# AX-03.net
KiCad netlist of a schematic drawn in EAGLE
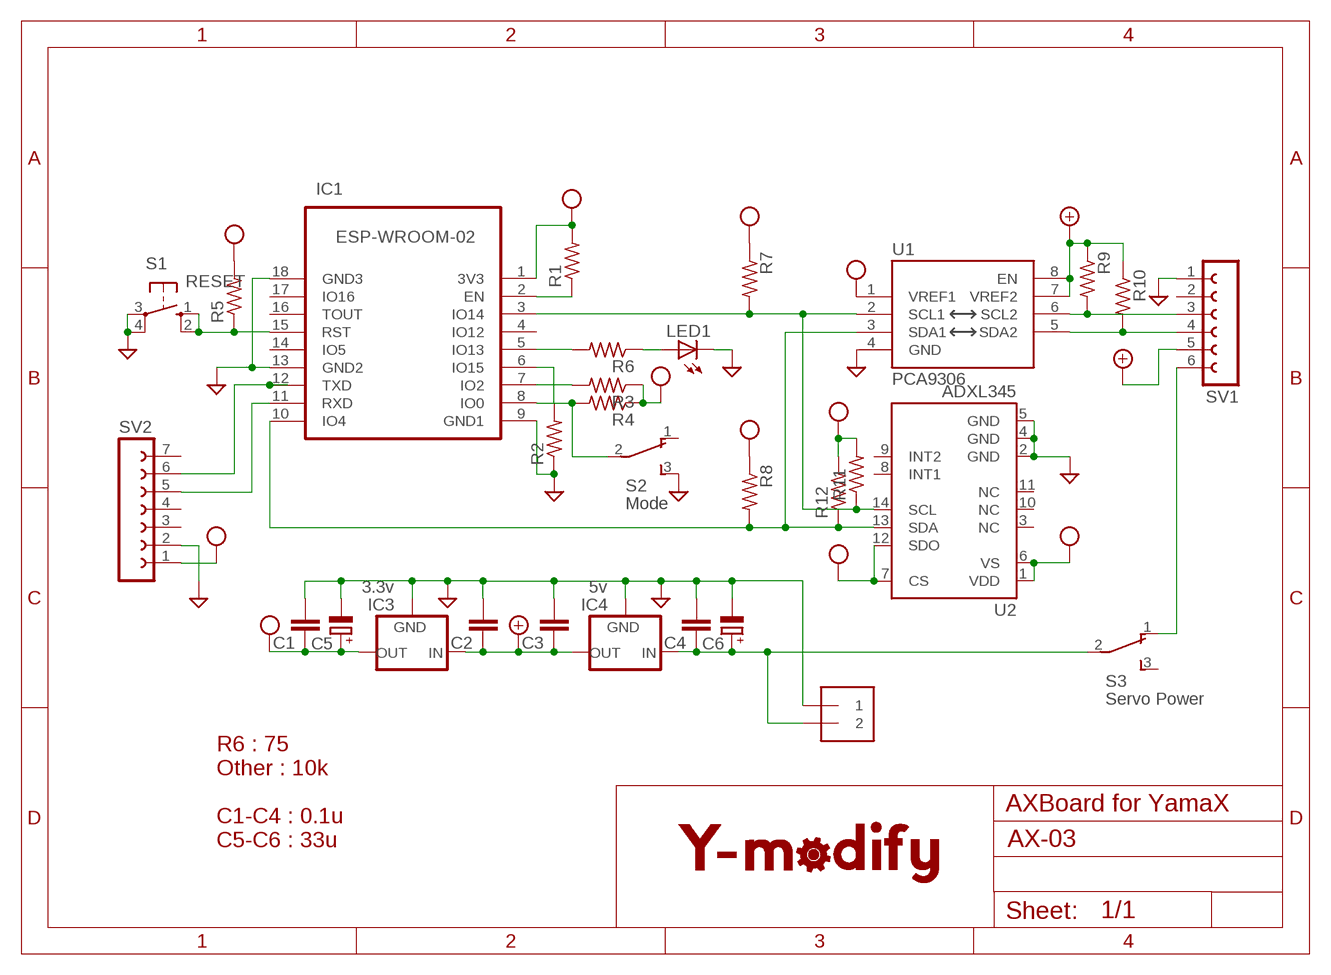
[diagram p0: schematic, sheet 1]

(export (version "E")
  (design (tool "Eeschema 10.0.6"))
  (components
    (comp (ref "C1")
      (value "C-EU025-024X044")
      (footprint "eagle-import:C025-024X044")
      (libsource (lib "eagle-import") (part "C-EU025-024X044"))
    )
    (comp (ref "C2")
      (value "C-EU025-024X044")
      (footprint "eagle-import:C025-024X044")
      (libsource (lib "eagle-import") (part "C-EU025-024X044"))
    )
    (comp (ref "C3")
      (value "C-EU025-024X044")
      (footprint "eagle-import:C025-024X044")
      (libsource (lib "eagle-import") (part "C-EU025-024X044"))
    )
    (comp (ref "C4")
      (value "C-EU025-024X044")
      (footprint "eagle-import:C025-024X044")
      (libsource (lib "eagle-import") (part "C-EU025-024X044"))
    )
    (comp (ref "C5")
      (value "CPOL-EUE5-8.5")
      (footprint "eagle-import:E5-8,5")
      (libsource (lib "eagle-import") (part "CPOL-EUE5-8.5"))
    )
    (comp (ref "C6")
      (value "CPOL-EUE5-8.5")
      (footprint "eagle-import:E5-8,5")
      (libsource (lib "eagle-import") (part "CPOL-EUE5-8.5"))
    )
    (comp (ref "IC1")
      (value "ESP-WROOM-02")
      (footprint "eagle-import:FRONT-FACE")
      (libsource (lib "eagle-import") (part "ESP-WROOM-02FRONT-FACE"))
    )
    (comp (ref "IC3")
      (value "3.3v")
      (footprint "eagle-import:78XXL")
      (libsource (lib "eagle-import") (part "78XXL"))
    )
    (comp (ref "IC4")
      (value "5v")
      (footprint "eagle-import:78XXL")
      (libsource (lib "eagle-import") (part "78XXL"))
    )
    (comp (ref "J1")
      (value "1X2-3.5MM")
      (footprint "eagle-import:1X2-3.5MM")
      (libsource (lib "eagle-import") (part "1X2-3.5MM"))
    )
    (comp (ref "LED1")
      (value "LED3MM")
      (footprint "eagle-import:LED3MM")
      (libsource (lib "eagle-import") (part "LED3MM"))
    )
    (comp (ref "R1")
      (value "R-US_0204/7")
      (footprint "eagle-import:0204_7")
      (libsource (lib "eagle-import") (part "R-US_0204/7"))
    )
    (comp (ref "R2")
      (value "R-US_0204/7")
      (footprint "eagle-import:0204_7")
      (libsource (lib "eagle-import") (part "R-US_0204/7"))
    )
    (comp (ref "R3")
      (value "R-US_0204/7")
      (footprint "eagle-import:0204_7")
      (libsource (lib "eagle-import") (part "R-US_0204/7"))
    )
    (comp (ref "R4")
      (value "R-US_0204/7")
      (footprint "eagle-import:0204_7")
      (libsource (lib "eagle-import") (part "R-US_0204/7"))
    )
    (comp (ref "R5")
      (value "R-US_0204/7")
      (footprint "eagle-import:0204_7")
      (libsource (lib "eagle-import") (part "R-US_0204/7"))
    )
    (comp (ref "R6")
      (value "R-US_0204/7")
      (footprint "eagle-import:0204_7")
      (libsource (lib "eagle-import") (part "R-US_0204/7"))
    )
    (comp (ref "R7")
      (value "R-US_0204/7")
      (footprint "eagle-import:0204_7")
      (libsource (lib "eagle-import") (part "R-US_0204/7"))
    )
    (comp (ref "R8")
      (value "R-US_0204/7")
      (footprint "eagle-import:0204_7")
      (libsource (lib "eagle-import") (part "R-US_0204/7"))
    )
    (comp (ref "R9")
      (value "R-US_0204/7")
      (footprint "eagle-import:0204_7")
      (libsource (lib "eagle-import") (part "R-US_0204/7"))
    )
    (comp (ref "R10")
      (value "R-US_0204/7")
      (footprint "eagle-import:0204_7")
      (libsource (lib "eagle-import") (part "R-US_0204/7"))
    )
    (comp (ref "R11")
      (value "R-US_0204/7")
      (footprint "eagle-import:0204_7")
      (libsource (lib "eagle-import") (part "R-US_0204/7"))
    )
    (comp (ref "R12")
      (value "R-US_0204/7")
      (footprint "eagle-import:0204_7")
      (libsource (lib "eagle-import") (part "R-US_0204/7"))
    )
    (comp (ref "S1")
      (value "RESET")
      (footprint "eagle-import:B3F-10XX")
      (fields (field (name "MPN") "B3F-1000"))
      (libsource (lib "eagle-import") (part "10-XX"))
    )
    (comp (ref "S2")
      (value "Mode")
      (footprint "eagle-import:TL3XYO")
      (libsource (lib "eagle-import") (part "TL36YO"))
    )
    (comp (ref "S3")
      (value "Servo Power")
      (footprint "eagle-import:TL3XYO")
      (libsource (lib "eagle-import") (part "TL36YO"))
    )
    (comp (ref "SV1")
      (value "FE06-1")
      (footprint "eagle-import:FE06")
      (libsource (lib "eagle-import") (part "FE06-1"))
    )
    (comp (ref "SV2")
      (value "FE07-1")
      (footprint "eagle-import:FE07")
      (libsource (lib "eagle-import") (part "FE07-1"))
    )
    (comp (ref "U$1")
      (value "Y-MODIFY")
      (footprint "eagle-import:Y-MODIFY")
      (libsource (lib "eagle-import") (part "Y-MODIFY"))
    )
    (comp (ref "U1")
      (value "PCA9306")
      (footprint "eagle-import:PSOP-8")
      (libsource (lib "eagle-import") (part "PCA9306"))
    )
    (comp (ref "U2")
      (value "ADXL345")
      (footprint "eagle-import:LGA14")
      (libsource (lib "eagle-import") (part "ADXL345"))
    )
  )
  (nets
    (net (code "1") (name "+5V") (class "Default")
      (node (ref "C2") (pin "1") (pinfunction "1_1") (pintype "passive"))
      (node (ref "C3") (pin "1") (pinfunction "1_1") (pintype "passive"))
      (node (ref "IC3") (pin "IN") (pinfunction "IN_IN") (pintype "input"))
      (node (ref "IC4") (pin "OUT") (pinfunction "OUT_OUT") (pintype "passive"))
      (node (ref "R10") (pin "1") (pinfunction "1_1") (pintype "passive"))
      (node (ref "R9") (pin "1") (pinfunction "1_1") (pintype "passive"))
      (node (ref "SV1") (pin "5") (pinfunction "5_5") (pintype "passive"))
      (node (ref "U1") (pin "7") (pinfunction "VREF2_7") (pintype "bidirectional"))
      (node (ref "U1") (pin "8") (pinfunction "EN_8") (pintype "bidirectional"))
    )
    (net (code "2") (name "GND") (class "Default")
      (node (ref "C1") (pin "2") (pinfunction "2_2") (pintype "passive"))
      (node (ref "C2") (pin "2") (pinfunction "2_2") (pintype "passive"))
      (node (ref "C3") (pin "2") (pinfunction "2_2") (pintype "passive"))
      (node (ref "C4") (pin "2") (pinfunction "2_2") (pintype "passive"))
      (node (ref "C5") (pin "-") (pinfunction "-_-") (pintype "passive"))
      (node (ref "C6") (pin "-") (pinfunction "-_-") (pintype "passive"))
      (node (ref "IC1") (pin "13") (pinfunction "GND2_13") (pintype "power_in"))
      (node (ref "IC1") (pin "18") (pinfunction "GND3_18") (pintype "power_in"))
      (node (ref "IC1") (pin "9") (pinfunction "GND1_9") (pintype "power_in"))
      (node (ref "IC3") (pin "GND") (pinfunction "GND_GND") (pintype "input"))
      (node (ref "IC4") (pin "GND") (pinfunction "GND_GND") (pintype "input"))
      (node (ref "J1") (pin "1") (pinfunction "1_1") (pintype "passive"))
      (node (ref "LED1") (pin "K") (pinfunction "C_K") (pintype "passive"))
      (node (ref "R2") (pin "1") (pinfunction "1_1") (pintype "passive"))
      (node (ref "S1") (pin "3") (pinfunction "P_3") (pintype "passive"))
      (node (ref "S1") (pin "4") (pinfunction "P1_4") (pintype "passive"))
      (node (ref "S2") (pin "3") (pinfunction "S_3") (pintype "passive"))
      (node (ref "SV1") (pin "1") (pinfunction "1_1") (pintype "passive"))
      (node (ref "SV2") (pin "2") (pinfunction "2_2") (pintype "passive"))
      (node (ref "U1") (pin "4") (pinfunction "GND_4") (pintype "bidirectional"))
      (node (ref "U2") (pin "2") (pinfunction "GND_2") (pintype "bidirectional"))
      (node (ref "U2") (pin "4") (pinfunction "GND_4") (pintype "bidirectional"))
      (node (ref "U2") (pin "5") (pinfunction "GND_5") (pintype "bidirectional"))
    )
    (net (code "3") (name "Net-(IC1-EN)") (class "Default")
      (node (ref "IC1") (pin "2") (pinfunction "EN_2") (pintype "bidirectional"))
      (node (ref "R1") (pin "1") (pinfunction "1_1") (pintype "passive"))
    )
    (net (code "4") (name "Net-(IC1-IO0)") (class "Default")
      (node (ref "IC1") (pin "8") (pinfunction "IO0_8") (pintype "bidirectional"))
      (node (ref "R4") (pin "2") (pinfunction "2_2") (pintype "passive"))
      (node (ref "S2") (pin "2") (pinfunction "P_2") (pintype "passive"))
    )
    (net (code "5") (name "Net-(IC1-IO2)") (class "Default")
      (node (ref "IC1") (pin "7") (pinfunction "IO2_7") (pintype "bidirectional"))
      (node (ref "R3") (pin "2") (pinfunction "2_2") (pintype "passive"))
    )
    (net (code "6") (name "Net-(IC1-IO4)") (class "Default")
      (node (ref "IC1") (pin "10") (pinfunction "IO4_10") (pintype "bidirectional"))
      (node (ref "R12") (pin "1") (pinfunction "1_1") (pintype "passive"))
      (node (ref "R8") (pin "2") (pinfunction "2_2") (pintype "passive"))
      (node (ref "U1") (pin "3") (pinfunction "SDA1_3") (pintype "bidirectional"))
      (node (ref "U2") (pin "13") (pinfunction "SDA_13") (pintype "bidirectional"))
    )
    (net (code "7") (name "Net-(IC1-IO13)") (class "Default")
      (node (ref "IC1") (pin "5") (pinfunction "IO13_5") (pintype "bidirectional"))
      (node (ref "R6") (pin "2") (pinfunction "2_2") (pintype "passive"))
    )
    (net (code "8") (name "Net-(IC1-IO14)") (class "Default")
      (node (ref "IC1") (pin "3") (pinfunction "IO14_3") (pintype "bidirectional"))
      (node (ref "R11") (pin "1") (pinfunction "1_1") (pintype "passive"))
      (node (ref "R7") (pin "2") (pinfunction "2_2") (pintype "passive"))
      (node (ref "U1") (pin "2") (pinfunction "SCL1_2") (pintype "bidirectional"))
      (node (ref "U2") (pin "14") (pinfunction "SCL_14") (pintype "bidirectional"))
    )
    (net (code "9") (name "Net-(IC1-IO15)") (class "Default")
      (node (ref "IC1") (pin "6") (pinfunction "IO15_6") (pintype "bidirectional"))
      (node (ref "R2") (pin "2") (pinfunction "2_2") (pintype "passive"))
    )
    (net (code "10") (name "Net-(IC1-RST)") (class "Default")
      (node (ref "IC1") (pin "15") (pinfunction "RST_15") (pintype "bidirectional"))
      (node (ref "R5") (pin "1") (pinfunction "1_1") (pintype "passive"))
      (node (ref "S1") (pin "1") (pinfunction "S_1") (pintype "passive"))
      (node (ref "S1") (pin "2") (pinfunction "S1_2") (pintype "passive"))
    )
    (net (code "11") (name "Net-(IC1-RXD)") (class "Default")
      (node (ref "IC1") (pin "11") (pinfunction "RXD_11") (pintype "bidirectional"))
      (node (ref "SV2") (pin "5") (pinfunction "5_5") (pintype "passive"))
    )
    (net (code "12") (name "Net-(IC1-TXD)") (class "Default")
      (node (ref "IC1") (pin "12") (pinfunction "TXD_12") (pintype "bidirectional"))
      (node (ref "SV2") (pin "6") (pinfunction "6_6") (pintype "passive"))
    )
    (net (code "13") (name "Net-(LED1-PadA)") (class "Default")
      (node (ref "LED1") (pin "A") (pinfunction "A_A") (pintype "passive"))
      (node (ref "R6") (pin "1") (pinfunction "1_1") (pintype "passive"))
    )
    (net (code "14") (name "Net-(S3-O)") (class "Default")
      (node (ref "S3") (pin "1") (pinfunction "O_1") (pintype "passive"))
      (node (ref "SV1") (pin "6") (pinfunction "6_6") (pintype "passive"))
    )
    (net (code "15") (name "Net-(S3-P)") (class "Default")
      (node (ref "C4") (pin "1") (pinfunction "1_1") (pintype "passive"))
      (node (ref "C6") (pin "+") (pinfunction "+_+") (pintype "passive"))
      (node (ref "IC4") (pin "IN") (pinfunction "IN_IN") (pintype "input"))
      (node (ref "J1") (pin "2") (pinfunction "2_2") (pintype "passive"))
      (node (ref "S3") (pin "2") (pinfunction "P_2") (pintype "passive"))
    )
    (net (code "16") (name "Net-(U1-SCL2)") (class "Default")
      (node (ref "R9") (pin "2") (pinfunction "2_2") (pintype "passive"))
      (node (ref "SV1") (pin "3") (pinfunction "3_3") (pintype "passive"))
      (node (ref "U1") (pin "6") (pinfunction "SCL2_6") (pintype "bidirectional"))
    )
    (net (code "17") (name "Net-(U1-SDA2)") (class "Default")
      (node (ref "R10") (pin "2") (pinfunction "2_2") (pintype "passive"))
      (node (ref "SV1") (pin "4") (pinfunction "4_4") (pintype "passive"))
      (node (ref "U1") (pin "5") (pinfunction "SDA2_5") (pintype "bidirectional"))
    )
    (net (code "18") (name "VCC") (class "Default")
      (node (ref "C1") (pin "1") (pinfunction "1_1") (pintype "passive"))
      (node (ref "C5") (pin "+") (pinfunction "+_+") (pintype "passive"))
      (node (ref "IC1") (pin "1") (pinfunction "3V3_1") (pintype "power_in"))
      (node (ref "IC3") (pin "OUT") (pinfunction "OUT_OUT") (pintype "passive"))
      (node (ref "R1") (pin "2") (pinfunction "2_2") (pintype "passive"))
      (node (ref "R11") (pin "2") (pinfunction "2_2") (pintype "passive"))
      (node (ref "R12") (pin "2") (pinfunction "2_2") (pintype "passive"))
      (node (ref "R3") (pin "1") (pinfunction "1_1") (pintype "passive"))
      (node (ref "R4") (pin "1") (pinfunction "1_1") (pintype "passive"))
      (node (ref "R5") (pin "2") (pinfunction "2_2") (pintype "passive"))
      (node (ref "R7") (pin "1") (pinfunction "1_1") (pintype "passive"))
      (node (ref "R8") (pin "1") (pinfunction "1_1") (pintype "passive"))
      (node (ref "SV2") (pin "1") (pinfunction "1_1") (pintype "passive"))
      (node (ref "U1") (pin "1") (pinfunction "VREF1_1") (pintype "bidirectional"))
      (node (ref "U2") (pin "1") (pinfunction "VDD_1") (pintype "bidirectional"))
      (node (ref "U2") (pin "12") (pinfunction "SDO_12") (pintype "bidirectional"))
      (node (ref "U2") (pin "6") (pinfunction "VS_6") (pintype "bidirectional"))
      (node (ref "U2") (pin "7") (pinfunction "CS_7") (pintype "bidirectional"))
    )
    (net (code "19") (name "unconnected-(IC1-IO5-Pad14)") (class "Default")
      (node (ref "IC1") (pin "14") (pinfunction "IO5_14") (pintype "open_collector"))
    )
    (net (code "20") (name "unconnected-(IC1-IO12-Pad4)") (class "Default")
      (node (ref "IC1") (pin "4") (pinfunction "IO12_4") (pintype "bidirectional"))
    )
    (net (code "21") (name "unconnected-(IC1-IO16-Pad17)") (class "Default")
      (node (ref "IC1") (pin "17") (pinfunction "IO16_17") (pintype "bidirectional"))
    )
    (net (code "22") (name "unconnected-(IC1-TOUT-Pad16)") (class "Default")
      (node (ref "IC1") (pin "16") (pinfunction "TOUT_16") (pintype "bidirectional"))
    )
    (net (code "23") (name "unconnected-(S2-O-Pad1)") (class "Default")
      (node (ref "S2") (pin "1") (pinfunction "O_1") (pintype "passive"))
    )
    (net (code "24") (name "unconnected-(S3-S-Pad3)") (class "Default")
      (node (ref "S3") (pin "3") (pinfunction "S_3") (pintype "passive"))
    )
    (net (code "25") (name "unconnected-(SV1-Pad2)") (class "Default")
      (node (ref "SV1") (pin "2") (pinfunction "2_2") (pintype "passive"))
    )
    (net (code "26") (name "unconnected-(SV2-Pad3)") (class "Default")
      (node (ref "SV2") (pin "3") (pinfunction "3_3") (pintype "passive"))
    )
    (net (code "27") (name "unconnected-(SV2-Pad4)") (class "Default")
      (node (ref "SV2") (pin "4") (pinfunction "4_4") (pintype "passive"))
    )
    (net (code "28") (name "unconnected-(SV2-Pad7)") (class "Default")
      (node (ref "SV2") (pin "7") (pinfunction "7_7") (pintype "passive"))
    )
    (net (code "29") (name "unconnected-(U2-INT1-Pad8)") (class "Default")
      (node (ref "U2") (pin "8") (pinfunction "INT1_8") (pintype "bidirectional"))
    )
    (net (code "30") (name "unconnected-(U2-INT2-Pad9)") (class "Default")
      (node (ref "U2") (pin "9") (pinfunction "INT2_9") (pintype "bidirectional"))
    )
    (net (code "31") (name "unconnected-(U2-NC-Pad3)") (class "Default")
      (node (ref "U2") (pin "3") (pinfunction "NC_3") (pintype "bidirectional"))
    )
    (net (code "32") (name "unconnected-(U2-NC-Pad10)") (class "Default")
      (node (ref "U2") (pin "10") (pinfunction "NC_10") (pintype "bidirectional"))
    )
    (net (code "33") (name "unconnected-(U2-NC-Pad11)") (class "Default")
      (node (ref "U2") (pin "11") (pinfunction "NC_11") (pintype "bidirectional"))
    )
  )
)
